# power.net
KiCad netlist of a schematic drawn in Altium Designer
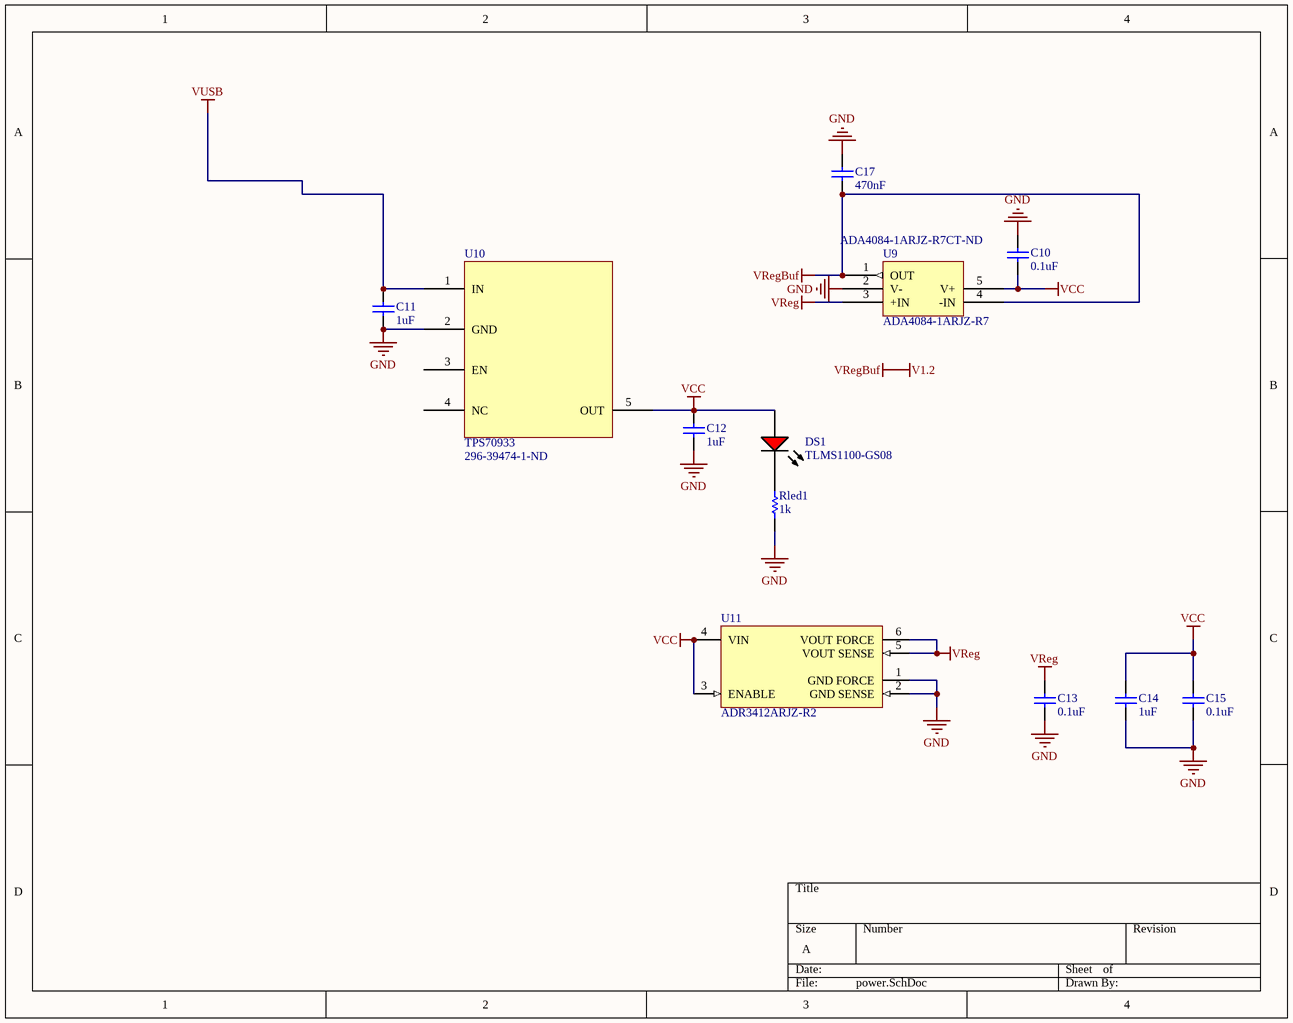
[diagram p0: power.SchDoc]

(export (version "E")
  (design (tool "Eeschema 10.0.6"))
  (components
    (comp (ref "C10")
      (value "0.1uF")
      (footprint "0402")
      (description "Ceramic Capacitor (Surface Mount)")
      (fields (field (name "MANUFACTURER") "Generic Ceramic Chip Cap (TBD)") (field (name "Comment") "Cap"))
      (libsource (lib "maglib") (part "Cap"))
    )
    (comp (ref "C11")
      (value "1uF")
      (footprint "0402")
      (description "Ceramic Capacitor (Surface Mount)")
      (fields (field (name "MANUFACTURER") "Generic Ceramic Chip Cap (TBD)") (field (name "Comment") "Cap"))
      (libsource (lib "maglib") (part "Cap"))
    )
    (comp (ref "C12")
      (value "1uF")
      (footprint "0402")
      (description "Ceramic Capacitor (Surface Mount)")
      (fields (field (name "MANUFACTURER") "Generic Ceramic Chip Cap (TBD)") (field (name "Comment") "Cap"))
      (libsource (lib "maglib") (part "Cap"))
    )
    (comp (ref "C13")
      (value "0.1uF")
      (footprint "0402")
      (description "Ceramic Capacitor (Surface Mount)")
      (fields (field (name "MANUFACTURER") "Generic Ceramic Chip Cap (TBD)") (field (name "Comment") "Cap"))
      (libsource (lib "maglib") (part "Cap"))
    )
    (comp (ref "C14")
      (value "1uF")
      (footprint "0402")
      (description "Ceramic Capacitor (Surface Mount)")
      (fields (field (name "MANUFACTURER") "Generic Ceramic Chip Cap (TBD)") (field (name "Comment") "Cap"))
      (libsource (lib "maglib") (part "Cap"))
    )
    (comp (ref "C15")
      (value "0.1uF")
      (footprint "0402")
      (description "Ceramic Capacitor (Surface Mount)")
      (fields (field (name "MANUFACTURER") "Generic Ceramic Chip Cap (TBD)") (field (name "Comment") "Cap"))
      (libsource (lib "maglib") (part "Cap"))
    )
    (comp (ref "C17")
      (value "470nF")
      (footprint "0402")
      (description "Ceramic Capacitor (Surface Mount)")
      (fields (field (name "MANUFACTURER") "Generic Ceramic Chip Cap (TBD)") (field (name "Comment") "Cap"))
      (libsource (lib "nextgaze") (part "Cap"))
    )
    (comp (ref "DS1")
      (value "TLMS1100-GS08")
      (footprint "VISH-TLMX1100_V")
      (description "LED, RED, 2.1 V, -40 to 100 degC, 2-Pin SMD (0603), RoHS, Tape and Reel")
      (fields (field (name "TOLERANCE") "5%"))
      (libsource (lib "Altium Content Vault") (part "LED-RED-AK-2"))
    )
    (comp (ref "Rled1")
      (value "1k")
      (footprint "0402")
      (description "Chip Resistor (Surface Mount)")
      (fields (field (name "MANUFACTURER") "Generic Chip Res (TBD)") (field (name "Comment") "Res"))
      (libsource (lib "maglib") (part "Res"))
    )
    (comp (ref "U9")
      (value "ADA4084-1ARJZ-R7")
      (footprint "SOT95P280X145-5N")
      (description "30 V, 8 MHz, Low Bias Current,\r\nSingle-Supply, RRO, Precision Op Amps")
      (fields (field (name "SUPPLIER PART NUMBER 1") "ADA4084-1ARJZ-R7CT-ND"))
      (libsource (lib "maglib") (part "ADA4622-1ARJZ"))
    )
    (comp (ref "U10")
      (value "TPS70933")
      (footprint "SOT95P280X145-5N")
      (description "3.3V Ultra low power Voltage Regulator")
      (fields (field (name "SUPPLIER PART NUMBER 1") "296-39474-1-ND"))
      (libsource (lib "maglib") (part "TPS70933"))
    )
    (comp (ref "U11")
      (value "ADR3412ARJZ-R2")
      (footprint "ADI-RJ-6_N")
      (fields (field (name "MANUFACTURER") "Analog Devices"))
      (libsource (lib "Altium Content Vault") (part "ADI-ADR34xx-RJ-6"))
    )
  )
  (nets
    (net (code "1") (name "GND") (class "Default")
      (node (ref "C10") (pin "2") (pinfunction "2_2") (pintype "passive"))
      (node (ref "C11") (pin "2") (pinfunction "2_2") (pintype "passive"))
      (node (ref "C12") (pin "2") (pinfunction "2_2") (pintype "passive"))
      (node (ref "C13") (pin "1") (pinfunction "1_1") (pintype "passive"))
      (node (ref "C14") (pin "2") (pinfunction "2_2") (pintype "passive"))
      (node (ref "C15") (pin "1") (pinfunction "1_1") (pintype "passive"))
      (node (ref "C17") (pin "2") (pinfunction "2_2") (pintype "passive"))
      (node (ref "Rled1") (pin "1") (pinfunction "1_1") (pintype "passive"))
      (node (ref "U10") (pin "2") (pinfunction "GND_2") (pintype "passive"))
      (node (ref "U11") (pin "1") (pinfunction "GND_FORCE_1") (pintype "power_in"))
      (node (ref "U11") (pin "2") (pinfunction "GND_SENSE_2") (pintype "input"))
      (node (ref "U9") (pin "2") (pinfunction "V-_2") (pintype "power_in"))
    )
    (net (code "2") (name "Net-(DS1-K)") (class "Default")
      (node (ref "DS1") (pin "2") (pinfunction "K_2") (pintype "passive"))
      (node (ref "Rled1") (pin "2") (pinfunction "2_2") (pintype "passive"))
    )
    (net (code "3") (name "V1.2") (class "Default")
      (node (ref "C17") (pin "1") (pinfunction "1_1") (pintype "passive"))
      (node (ref "U9") (pin "1") (pinfunction "OUT_1") (pintype "output"))
      (node (ref "U9") (pin "4") (pinfunction "-IN_4") (pintype "passive"))
    )
    (net (code "4") (name "VCC") (class "Default")
      (node (ref "C10") (pin "1") (pinfunction "1_1") (pintype "passive"))
      (node (ref "C12") (pin "1") (pinfunction "1_1") (pintype "passive"))
      (node (ref "C14") (pin "1") (pinfunction "1_1") (pintype "passive"))
      (node (ref "C15") (pin "2") (pinfunction "2_2") (pintype "passive"))
      (node (ref "DS1") (pin "1") (pinfunction "A_1") (pintype "passive"))
      (node (ref "U10") (pin "5") (pinfunction "OUT_5") (pintype "passive"))
      (node (ref "U11") (pin "3") (pinfunction "ENABLE_3") (pintype "input"))
      (node (ref "U11") (pin "4") (pinfunction "VIN_4") (pintype "power_in"))
      (node (ref "U9") (pin "5") (pinfunction "V+_5") (pintype "power_in"))
    )
    (net (code "5") (name "VReg") (class "Default")
      (node (ref "C13") (pin "2") (pinfunction "2_2") (pintype "passive"))
      (node (ref "U11") (pin "5") (pinfunction "VOUT_SENSE_5") (pintype "input"))
      (node (ref "U11") (pin "6") (pinfunction "VOUT_FORCE_6") (pintype "power_in"))
      (node (ref "U9") (pin "3") (pinfunction "+IN_3") (pintype "passive"))
    )
    (net (code "6") (name "VUSB") (class "Default")
      (node (ref "C11") (pin "1") (pinfunction "1_1") (pintype "passive"))
      (node (ref "U10") (pin "1") (pinfunction "IN_1") (pintype "passive"))
    )
    (net (code "7") (name "unconnected-(U10-EN-Pad3)") (class "Default")
      (node (ref "U10") (pin "3") (pinfunction "EN_3") (pintype "passive"))
    )
    (net (code "8") (name "unconnected-(U10-NC-Pad4)") (class "Default")
      (node (ref "U10") (pin "4") (pinfunction "NC_4") (pintype "passive"))
    )
  )
)
